# SD_CARD.net
KiCad netlist of a schematic drawn in Altium Designer
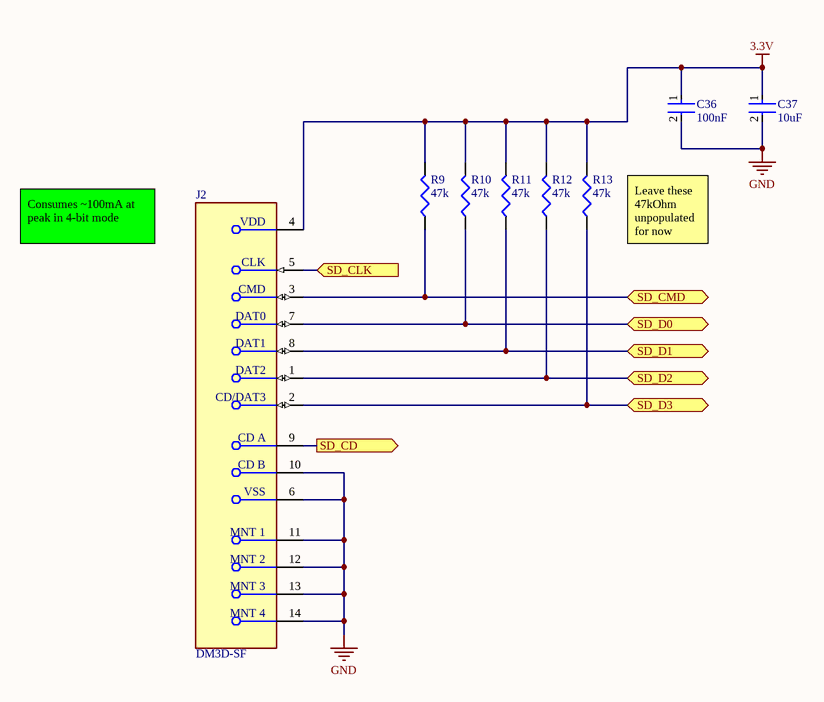
[diagram p0: SD_CARD.SchDoc]

(export (version "E")
  (design (tool "Eeschema 10.0.6"))
  (components
    (comp (ref "C36")
      (value "100nF")
      (footprint "FP-C0603C-CF-MFG")
      (description "Any 0603 Cap is fine here")
      (fields (field (name "TOLERANCE") "0.1") (field (name "MANUFACTURER") "KEMET"))
      (libsource (lib "Altium Content Vault") (part "b4654b650e69147ec39a6b967a45e02"))
    )
    (comp (ref "C37")
      (value "10uF")
      (footprint "FP-C0603C-CF-MFG")
      (description "Any 0603 Cap is fine here")
      (fields (field (name "TOLERANCE") "0.1") (field (name "MANUFACTURER") "KEMET"))
      (libsource (lib "Altium Content Vault") (part "b4654b650e69147ec39a6b967a45e02"))
    )
    (comp (ref "J2")
      (value "DM3D-SF")
      (footprint "FP-DM3D-SF-MFG")
      (description "CONN MICRO SD CARD PUSH-PULL")
      (libsource (lib "Altium Content Vault") (part "375756fe1061de806c40c19e9001ea3"))
    )
    (comp (ref "R9")
      (value "47k")
      (footprint "J1-0603")
      (description "Resistor")
      (fields (field (name "PUBLISHER") "Altium Limited"))
      (libsource (lib "Miscellaneous Devices") (part "Res3"))
    )
    (comp (ref "R10")
      (value "47k")
      (footprint "J1-0603")
      (description "Resistor")
      (fields (field (name "PUBLISHER") "Altium Limited"))
      (libsource (lib "Miscellaneous Devices") (part "Res3"))
    )
    (comp (ref "R11")
      (value "47k")
      (footprint "J1-0603")
      (description "Resistor")
      (fields (field (name "PUBLISHER") "Altium Limited"))
      (libsource (lib "Miscellaneous Devices") (part "Res3"))
    )
    (comp (ref "R12")
      (value "47k")
      (footprint "J1-0603")
      (description "Resistor")
      (fields (field (name "PUBLISHER") "Altium Limited"))
      (libsource (lib "Miscellaneous Devices") (part "Res3"))
    )
    (comp (ref "R13")
      (value "47k")
      (footprint "J1-0603")
      (description "Resistor")
      (fields (field (name "PUBLISHER") "Altium Limited"))
      (libsource (lib "Miscellaneous Devices") (part "Res3"))
    )
  )
  (nets
    (net (code "1") (name "/SD_CD") (class "Default")
      (node (ref "J2") (pin "9") (pinfunction "CD_A_9") (pintype "passive"))
    )
    (net (code "2") (name "/SD_CLK") (class "Default")
      (node (ref "J2") (pin "5") (pinfunction "CLK_5") (pintype "input"))
    )
    (net (code "3") (name "/SD_CMD") (class "Default")
      (node (ref "J2") (pin "3") (pinfunction "CMD_3") (pintype "bidirectional"))
      (node (ref "R9") (pin "1") (pinfunction "1_1") (pintype "passive"))
    )
    (net (code "4") (name "/SD_D0") (class "Default")
      (node (ref "J2") (pin "7") (pinfunction "DAT0_7") (pintype "bidirectional"))
      (node (ref "R10") (pin "1") (pinfunction "1_1") (pintype "passive"))
    )
    (net (code "5") (name "/SD_D1") (class "Default")
      (node (ref "J2") (pin "8") (pinfunction "DAT1_8") (pintype "bidirectional"))
      (node (ref "R11") (pin "1") (pinfunction "1_1") (pintype "passive"))
    )
    (net (code "6") (name "/SD_D2") (class "Default")
      (node (ref "J2") (pin "1") (pinfunction "DAT2_1") (pintype "bidirectional"))
      (node (ref "R12") (pin "1") (pinfunction "1_1") (pintype "passive"))
    )
    (net (code "7") (name "/SD_D3") (class "Default")
      (node (ref "J2") (pin "2") (pinfunction "CD/DAT3_2") (pintype "bidirectional"))
      (node (ref "R13") (pin "1") (pinfunction "1_1") (pintype "passive"))
    )
    (net (code "8") (name "3.3V") (class "Default")
      (node (ref "C36") (pin "1") (pinfunction "1_1") (pintype "passive"))
      (node (ref "C37") (pin "1") (pinfunction "1_1") (pintype "passive"))
      (node (ref "J2") (pin "4") (pinfunction "VDD_4") (pintype "power_in"))
      (node (ref "R10") (pin "2") (pinfunction "2_2") (pintype "passive"))
      (node (ref "R11") (pin "2") (pinfunction "2_2") (pintype "passive"))
      (node (ref "R12") (pin "2") (pinfunction "2_2") (pintype "passive"))
      (node (ref "R13") (pin "2") (pinfunction "2_2") (pintype "passive"))
      (node (ref "R9") (pin "2") (pinfunction "2_2") (pintype "passive"))
    )
    (net (code "9") (name "GND") (class "Default")
      (node (ref "C36") (pin "2") (pinfunction "2_2") (pintype "passive"))
      (node (ref "C37") (pin "2") (pinfunction "2_2") (pintype "passive"))
      (node (ref "J2") (pin "10") (pinfunction "CD_B_10") (pintype "passive"))
      (node (ref "J2") (pin "11") (pinfunction "MNT_1_11") (pintype "passive"))
      (node (ref "J2") (pin "12") (pinfunction "MNT_2_12") (pintype "passive"))
      (node (ref "J2") (pin "13") (pinfunction "MNT_3_13") (pintype "passive"))
      (node (ref "J2") (pin "14") (pinfunction "MNT_4_14") (pintype "passive"))
      (node (ref "J2") (pin "6") (pinfunction "VSS_6") (pintype "power_in"))
    )
  )
)
